# ADC.net
KiCad netlist of a schematic drawn in Altium Designer
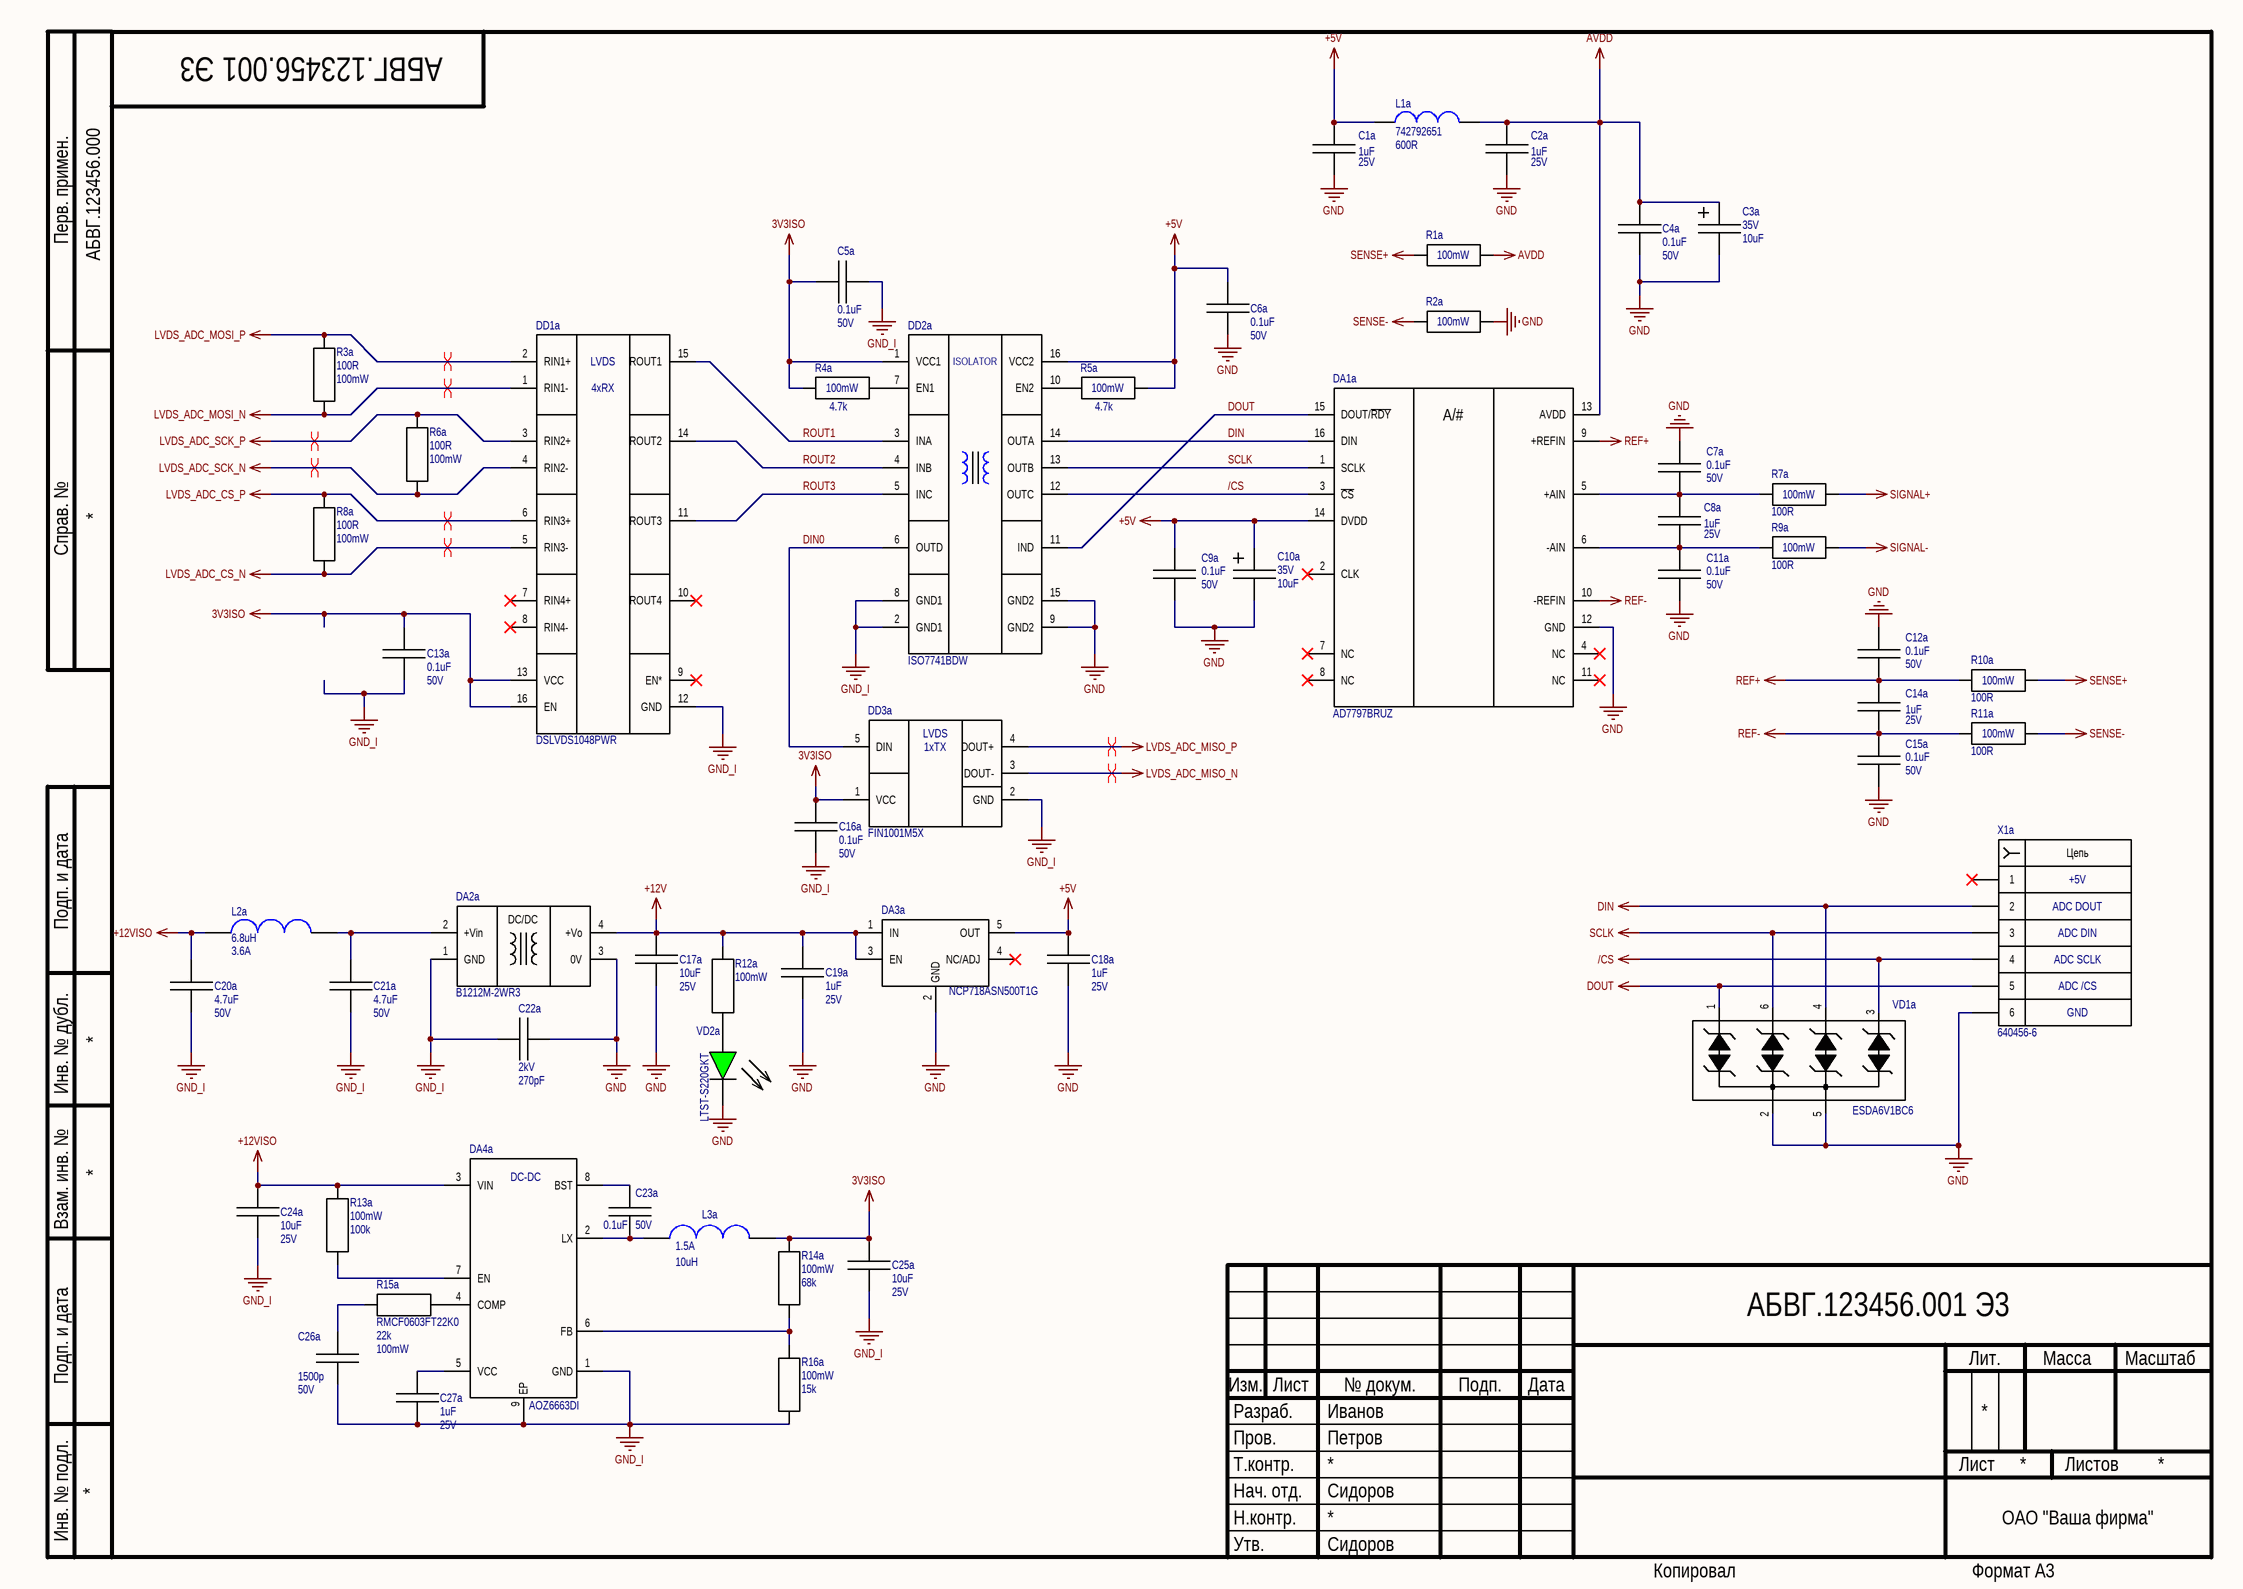
[diagram p0: ADC.SchDoc]

(export (version "E")
  (design (tool "Eeschema 10.0.6"))
  (components
    (comp (ref "C1a")
      (value "TMK107BJ105KA-T")
      (footprint "CAP 0603 IPC MAX")
      (description "CAP SMD CER 1UF 25V X5R 0603")
      (fields
        (field (name "TOLERANCE") "10%")
        (field (name "CAPACITANCE") "1uF")
        (field (name "RATED VOLTAGE") "25V")
      )
      (libsource (lib "Passive components") (part "TMK107BJ105KA-T"))
    )
    (comp (ref "C2a")
      (value "TMK107BJ105KA-T")
      (footprint "CAP 0603 IPC MAX")
      (description "CAP SMD CER 1UF 25V X5R 0603")
      (fields
        (field (name "TOLERANCE") "10%")
        (field (name "CAPACITANCE") "1uF")
        (field (name "RATED VOLTAGE") "25V")
      )
      (libsource (lib "Passive components") (part "TMK107BJ105KA-T"))
    )
    (comp (ref "C3a")
      (value "TAJD106M035RNJ")
      (footprint "CAP 2917 (D)")
      (description "CAP TANT 10UF 20% 35V 2917")
      (fields
        (field (name "TOLERANCE") "20%")
        (field (name "RATED VOLTAGE") "35V")
        (field (name "CAPACITANCE") "10uF")
      )
      (libsource (lib "Passive components") (part "TAJD106M035RNJ"))
    )
    (comp (ref "C4a")
      (value "GCM188R71H104KA57D")
      (footprint "CAP 0603 IPC MAX")
      (description "CAP SMD CER 0.1UF 50V X7R 0603")
      (fields
        (field (name "TOLERANCE") "10%")
        (field (name "CAPACITANCE") "0.1uF")
        (field (name "RATED VOLTAGE") "50V")
      )
      (libsource (lib "Passive components") (part "GCM188R71H104KA57D"))
    )
    (comp (ref "C5a")
      (value "GCM188R71H104KA57D")
      (footprint "CAP 0603 IPC MAX")
      (description "CAP SMD CER 0.1UF 50V X7R 0603")
      (fields
        (field (name "TOLERANCE") "10%")
        (field (name "CAPACITANCE") "0.1uF")
        (field (name "RATED VOLTAGE") "50V")
      )
      (libsource (lib "Passive components") (part "GCM188R71H104KA57D"))
    )
    (comp (ref "C6a")
      (value "GCM188R71H104KA57D")
      (footprint "CAP 0603 IPC MAX")
      (description "CAP SMD CER 0.1UF 50V X7R 0603")
      (fields
        (field (name "TOLERANCE") "10%")
        (field (name "CAPACITANCE") "0.1uF")
        (field (name "RATED VOLTAGE") "50V")
      )
      (libsource (lib "Passive components") (part "GCM188R71H104KA57D"))
    )
    (comp (ref "C7a")
      (value "GCM188R71H104KA57D")
      (footprint "CAP 0603 IPC MAX")
      (description "CAP SMD CER 0.1UF 50V X7R 0603")
      (fields
        (field (name "TOLERANCE") "10%")
        (field (name "CAPACITANCE") "0.1uF")
        (field (name "RATED VOLTAGE") "50V")
      )
      (libsource (lib "Passive components") (part "GCM188R71H104KA57D"))
    )
    (comp (ref "C8a")
      (value "TMK107BJ105KA-T")
      (footprint "CAP 0603 IPC MAX")
      (description "CAP SMD CER 1UF 25V X5R 0603")
      (fields
        (field (name "TOLERANCE") "10%")
        (field (name "CAPACITANCE") "1uF")
        (field (name "RATED VOLTAGE") "25V")
      )
      (libsource (lib "Passive components") (part "TMK107BJ105KA-T"))
    )
    (comp (ref "C9a")
      (value "GCM188R71H104KA57D")
      (footprint "CAP 0603 IPC MAX")
      (description "CAP SMD CER 0.1UF 50V X7R 0603")
      (fields
        (field (name "TOLERANCE") "10%")
        (field (name "CAPACITANCE") "0.1uF")
        (field (name "RATED VOLTAGE") "50V")
      )
      (libsource (lib "Passive components") (part "GCM188R71H104KA57D"))
    )
    (comp (ref "C10a")
      (value "TAJD106M035RNJ")
      (footprint "CAP 2917 (D)")
      (description "CAP TANT 10UF 20% 35V 2917")
      (fields
        (field (name "TOLERANCE") "20%")
        (field (name "RATED VOLTAGE") "35V")
        (field (name "CAPACITANCE") "10uF")
      )
      (libsource (lib "Passive components") (part "TAJD106M035RNJ"))
    )
    (comp (ref "C11a")
      (value "GCM188R71H104KA57D")
      (footprint "CAP 0603 IPC MAX")
      (description "CAP SMD CER 0.1UF 50V X7R 0603")
      (fields
        (field (name "TOLERANCE") "10%")
        (field (name "CAPACITANCE") "0.1uF")
        (field (name "RATED VOLTAGE") "50V")
      )
      (libsource (lib "Passive components") (part "GCM188R71H104KA57D"))
    )
    (comp (ref "C12a")
      (value "GCM188R71H104KA57D")
      (footprint "CAP 0603 IPC MAX")
      (description "CAP SMD CER 0.1UF 50V X7R 0603")
      (fields
        (field (name "TOLERANCE") "10%")
        (field (name "CAPACITANCE") "0.1uF")
        (field (name "RATED VOLTAGE") "50V")
      )
      (libsource (lib "Passive components") (part "GCM188R71H104KA57D"))
    )
    (comp (ref "C13a")
      (value "GCM188R71H104KA57D")
      (footprint "CAP 0603 IPC MAX")
      (description "CAP SMD CER 0.1UF 50V X7R 0603")
      (fields
        (field (name "TOLERANCE") "10%")
        (field (name "CAPACITANCE") "0.1uF")
        (field (name "RATED VOLTAGE") "50V")
      )
      (libsource (lib "Passive components") (part "GCM188R71H104KA57D"))
    )
    (comp (ref "C14a")
      (value "TMK107BJ105KA-T")
      (footprint "CAP 0603 IPC MAX")
      (description "CAP SMD CER 1UF 25V X5R 0603")
      (fields
        (field (name "TOLERANCE") "10%")
        (field (name "CAPACITANCE") "1uF")
        (field (name "RATED VOLTAGE") "25V")
      )
      (libsource (lib "Passive components") (part "TMK107BJ105KA-T"))
    )
    (comp (ref "C15a")
      (value "GCM188R71H104KA57D")
      (footprint "CAP 0603 IPC MAX")
      (description "CAP SMD CER 0.1UF 50V X7R 0603")
      (fields
        (field (name "TOLERANCE") "10%")
        (field (name "CAPACITANCE") "0.1uF")
        (field (name "RATED VOLTAGE") "50V")
      )
      (libsource (lib "Passive components") (part "GCM188R71H104KA57D"))
    )
    (comp (ref "C16a")
      (value "GCM188R71H104KA57D")
      (footprint "CAP 0603 IPC MAX")
      (description "CAP SMD CER 0.1UF 50V X7R 0603")
      (fields
        (field (name "TOLERANCE") "10%")
        (field (name "CAPACITANCE") "0.1uF")
        (field (name "RATED VOLTAGE") "50V")
      )
      (libsource (lib "Passive components") (part "GCM188R71H104KA57D"))
    )
    (comp (ref "C17a")
      (value "CL31B106KAHNNNE")
      (footprint "CAP 1206 IPC MAX")
      (description "CAP SMD CER 10UF 25V X7R 1206")
      (fields
        (field (name "TOLERANCE") "10%")
        (field (name "CAPACITANCE") "10uF")
        (field (name "RATED VOLTAGE") "25V")
      )
      (libsource (lib "Passive components") (part "CL31B106KAHNNNE"))
    )
    (comp (ref "C18a")
      (value "TMK107BJ105KA-T")
      (footprint "CAP 0603 IPC MAX")
      (description "CAP SMD CER 1UF 25V X5R 0603")
      (fields
        (field (name "TOLERANCE") "10%")
        (field (name "CAPACITANCE") "1uF")
        (field (name "RATED VOLTAGE") "25V")
      )
      (libsource (lib "Passive components") (part "TMK107BJ105KA-T"))
    )
    (comp (ref "C19a")
      (value "TMK107BJ105KA-T")
      (footprint "CAP 0603 IPC MAX")
      (description "CAP SMD CER 1UF 25V X5R 0603")
      (fields
        (field (name "TOLERANCE") "10%")
        (field (name "CAPACITANCE") "1uF")
        (field (name "RATED VOLTAGE") "25V")
      )
      (libsource (lib "Passive components") (part "TMK107BJ105KA-T"))
    )
    (comp (ref "C20a")
      (value "CL21A475KBQNNNE")
      (footprint "CAP 0805 IPC MAX")
      (description "CAP SMD CER 4.7UF 50V X5R 0805")
      (fields
        (field (name "TOLERANCE") "10%")
        (field (name "CAPACITANCE") "4.7uF")
        (field (name "RATED VOLTAGE") "50V")
      )
      (libsource (lib "Passive components") (part "CL21A475KBQNNNE"))
    )
    (comp (ref "C21a")
      (value "CL21A475KBQNNNE")
      (footprint "CAP 0805 IPC MAX")
      (description "CAP SMD CER 4.7UF 50V X5R 0805")
      (fields
        (field (name "TOLERANCE") "10%")
        (field (name "CAPACITANCE") "4.7uF")
        (field (name "RATED VOLTAGE") "50V")
      )
      (libsource (lib "Passive components") (part "CL21A475KBQNNNE"))
    )
    (comp (ref "C22a")
      (value "PHE448SB3270JR06")
      (footprint "CAP RADIAL L18.0 W5.0 H10.5 P15.0")
      (description "CAP FILM 270PF 5% 2KVDC RADIAL")
      (fields
        (field (name "TOLERANCE") "5%")
        (field (name "RATED VOLTAGE") "2kV")
        (field (name "CAPACITANCE") "270pF")
      )
      (libsource (lib "Passive components") (part "PHE448SB3270JR06"))
    )
    (comp (ref "C23a")
      (value "GCM188R71H104KA57D")
      (footprint "CAP 0603 IPC MAX")
      (description "CAP SMD CER 0.1UF 50V X7R 0603")
      (fields
        (field (name "TOLERANCE") "10%")
        (field (name "CAPACITANCE") "0.1uF")
        (field (name "RATED VOLTAGE") "50V")
      )
      (libsource (lib "Passive components") (part "GCM188R71H104KA57D"))
    )
    (comp (ref "C24a")
      (value "CL31B106KAHNNNE")
      (footprint "CAP 1206 IPC MAX")
      (description "CAP SMD CER 10UF 25V X7R 1206")
      (fields
        (field (name "TOLERANCE") "10%")
        (field (name "CAPACITANCE") "10uF")
        (field (name "RATED VOLTAGE") "25V")
      )
      (libsource (lib "Passive components") (part "CL31B106KAHNNNE"))
    )
    (comp (ref "C25a")
      (value "CL31B106KAHNNNE")
      (footprint "CAP 1206 IPC MAX")
      (description "CAP SMD CER 10UF 25V X7R 1206")
      (fields
        (field (name "TOLERANCE") "10%")
        (field (name "CAPACITANCE") "10uF")
        (field (name "RATED VOLTAGE") "25V")
      )
      (libsource (lib "Passive components") (part "CL31B106KAHNNNE"))
    )
    (comp (ref "C26a")
      (value "GRM1885C1H152JA01D")
      (footprint "CAP 0603 IPC MAX")
      (description "CAP SMD CER 1500PF 50V C0G/NP0 0603")
      (fields
        (field (name "TOLERANCE") "5%")
        (field (name "CAPACITANCE") "1500p")
        (field (name "RATED VOLTAGE") "50V")
      )
      (libsource (lib "Passive components") (part "GRM1885C1H152JA01D"))
    )
    (comp (ref "C27a")
      (value "TMK107BJ105KA-T")
      (footprint "CAP 0603 IPC MAX")
      (description "CAP SMD CER 1UF 25V X5R 0603")
      (fields
        (field (name "TOLERANCE") "10%")
        (field (name "CAPACITANCE") "1uF")
        (field (name "RATED VOLTAGE") "25V")
      )
      (libsource (lib "Passive components") (part "TMK107BJ105KA-T"))
    )
    (comp (ref "DA1a")
      (value "AD7797BRUZ")
      (footprint "TSSOP-16")
      (description "IC ADC 24BIT SIGMA-DELTA 16TSSOP")
      (libsource (lib "Digital") (part "AD7797BRUZ"))
    )
    (comp (ref "DA2a")
      (value "B1212M-2WR3")
      (footprint "B1212M-2WR3")
      (description "DC DC CONVERTER 12V 2W")
      (libsource (lib "Power") (part "B1212M-2WR3"))
    )
    (comp (ref "DA3a")
      (value "NCP718ASN500T1G")
      (footprint "TSOT-23-5")
      (description "IC REG LINEAR 5V 300MA TSOT23-5")
      (libsource (lib "Power") (part "NCP718ASN500T1G"))
    )
    (comp (ref "DA4a")
      (value "AOZ6663DI")
      (footprint "DFN 3x3-8L")
      (description "IC REG BUCK ADJ 3A 8DFN")
      (libsource (lib "Power") (part "AOZ6663DI"))
    )
    (comp (ref "DD1a")
      (value "DSLVDS1048PWR")
      (footprint "TSSOP-16")
      (description "IC RECEIVER LVDS FULL 0/4 16TSSOP")
      (libsource (lib "Digital") (part "DSLVDS1048PWR"))
    )
    (comp (ref "DD2a")
      (value "ISO7741BDW")
      (footprint "SOIC-16 IPC MAX")
      (description "DIG ISO - MYNA - QUAD")
      (libsource (lib "Digital") (part "ISO7741BDW"))
    )
    (comp (ref "DD3a")
      (value "FIN1001M5X")
      (footprint "SOT-23-5")
      (description "IC DRIVER LVDS 1/0 SOT23-5")
      (libsource (lib "Digital") (part "FIN1001M5X"))
    )
    (comp (ref "L1a")
      (value "742792651")
      (footprint "IND 0603 IPC MAX")
      (description "FERRITE BEAD 600 OHM 0603 1LN")
      (fields (field (name "INMEDANCE @ 100MHZ") "600R"))
      (libsource (lib "Passive components") (part "742792651"))
    )
    (comp (ref "L2a")
      (value "VLS6045EX-6R8M")
      (footprint "VLS6045EX")
      (description "FIXED IND 6.8UH 3.6A 36 MOHM SMD")
      (fields (field (name "INDUCTANCE") "6.8uH") (field (name "CURRENT RATING") "3.6A"))
      (libsource (lib "Passive components") (part "VLS6045EX-6R8M"))
    )
    (comp (ref "L3a")
      (value "ASPI-4030S-100M-T")
      (footprint "ASPI-4030S")
      (description "FIXED IND 10UH 1.5A 100 MOHM SMD")
      (fields (field (name "INDUCTANCE") "10uH") (field (name "CURRENT RATING") "1.5A"))
      (libsource (lib "Passive components") (part "ASPI-4030S-100M-T"))
    )
    (comp (ref "R1a")
      (value "RMCF0603ZT0R00")
      (footprint "RES 0603 IPC MAX")
      (description "RES SMD 0 OHM 1% 1/10W 0603")
      (fields (field (name "TOLERANCE") "1%") (field (name "RATED POWER") "100mW"))
      (libsource (lib "Passive components") (part "RMCF0603ZT0R00"))
    )
    (comp (ref "R2a")
      (value "RMCF0603ZT0R00")
      (footprint "RES 0603 IPC MAX")
      (description "RES SMD 0 OHM 1% 1/10W 0603")
      (fields (field (name "TOLERANCE") "1%") (field (name "RATED POWER") "100mW"))
      (libsource (lib "Passive components") (part "RMCF0603ZT0R00"))
    )
    (comp (ref "R3a")
      (value "RMCF0603FT100R")
      (footprint "RES 0603 IPC MAX")
      (description "RES SMD 100 OHM 1% 1/10W 0603")
      (fields
        (field (name "TOLERANCE") "1%")
        (field (name "RESISTANCE") "100R")
        (field (name "RATED POWER") "100mW")
      )
      (libsource (lib "Passive components") (part "RMCF0603FT100R"))
    )
    (comp (ref "R4a")
      (value "RMCF0603FT4K70")
      (footprint "RES 0603 IPC MAX")
      (description "RES SMD 4.7k OHM 1% 1/10W 0603")
      (fields
        (field (name "TOLERANCE") "1%")
        (field (name "RATED POWER") "100mW")
        (field (name "RESISTANCE") "4.7k")
      )
      (libsource (lib "Passive components") (part "RMCF0603FT4K70"))
    )
    (comp (ref "R5a")
      (value "RMCF0603FT4K70")
      (footprint "RES 0603 IPC MAX")
      (description "RES SMD 4.7k OHM 1% 1/10W 0603")
      (fields
        (field (name "TOLERANCE") "1%")
        (field (name "RATED POWER") "100mW")
        (field (name "RESISTANCE") "4.7k")
      )
      (libsource (lib "Passive components") (part "RMCF0603FT4K70"))
    )
    (comp (ref "R6a")
      (value "RMCF0603FT100R")
      (footprint "RES 0603 IPC MAX")
      (description "RES SMD 100 OHM 1% 1/10W 0603")
      (fields
        (field (name "TOLERANCE") "1%")
        (field (name "RESISTANCE") "100R")
        (field (name "RATED POWER") "100mW")
      )
      (libsource (lib "Passive components") (part "RMCF0603FT100R"))
    )
    (comp (ref "R7a")
      (value "RMCF0603FT100R")
      (footprint "RES 0603 IPC MAX")
      (description "RES SMD 100 OHM 1% 1/10W 0603")
      (fields
        (field (name "TOLERANCE") "1%")
        (field (name "RESISTANCE") "100R")
        (field (name "RATED POWER") "100mW")
      )
      (libsource (lib "Passive components") (part "RMCF0603FT100R"))
    )
    (comp (ref "R8a")
      (value "RMCF0603FT100R")
      (footprint "RES 0603 IPC MAX")
      (description "RES SMD 100 OHM 1% 1/10W 0603")
      (fields
        (field (name "TOLERANCE") "1%")
        (field (name "RESISTANCE") "100R")
        (field (name "RATED POWER") "100mW")
      )
      (libsource (lib "Passive components") (part "RMCF0603FT100R"))
    )
    (comp (ref "R9a")
      (value "RMCF0603FT100R")
      (footprint "RES 0603 IPC MAX")
      (description "RES SMD 100 OHM 1% 1/10W 0603")
      (fields
        (field (name "TOLERANCE") "1%")
        (field (name "RESISTANCE") "100R")
        (field (name "RATED POWER") "100mW")
      )
      (libsource (lib "Passive components") (part "RMCF0603FT100R"))
    )
    (comp (ref "R10a")
      (value "RMCF0603FT100R")
      (footprint "RES 0603 IPC MAX")
      (description "RES SMD 100 OHM 1% 1/10W 0603")
      (fields
        (field (name "TOLERANCE") "1%")
        (field (name "RESISTANCE") "100R")
        (field (name "RATED POWER") "100mW")
      )
      (libsource (lib "Passive components") (part "RMCF0603FT100R"))
    )
    (comp (ref "R11a")
      (value "RMCF0603FT100R")
      (footprint "RES 0603 IPC MAX")
      (description "RES SMD 100 OHM 1% 1/10W 0603")
      (fields
        (field (name "TOLERANCE") "1%")
        (field (name "RESISTANCE") "100R")
        (field (name "RATED POWER") "100mW")
      )
      (libsource (lib "Passive components") (part "RMCF0603FT100R"))
    )
    (comp (ref "R12a")
      (value "RMCF0603FT2K00")
      (footprint "RES 0603 IPC MAX")
      (description "RES SMD 2K OHM 1% 1/10W 0603")
      (fields (field (name "TOLERANCE") "1%") (field (name "RATED POWER") "100mW"))
      (libsource (lib "Passive components") (part "RMCF0603FT2K00"))
    )
    (comp (ref "R13a")
      (value "RMCF0603FT100K")
      (footprint "RES 0603 IPC MAX")
      (description "RES SMD 100K OHM 5% 1/10W 0603")
      (fields
        (field (name "TOLERANCE") "5%")
        (field (name "POWER RATED") "100mW")
        (field (name "RESISTANCE") "100k")
      )
      (libsource (lib "Passive components") (part "RMCF0603FT100K"))
    )
    (comp (ref "R14a")
      (value "RMCF0603FT68K0")
      (footprint "RES 0603 IPC MAX")
      (description "RES SMD 68K OHM 1% 1/10W 0603")
      (fields
        (field (name "TOLERANCE") "1%")
        (field (name "POWER RATED") "100mW")
        (field (name "RESISTANCE") "68k")
      )
      (libsource (lib "Passive components") (part "RMCF0603FT68K0"))
    )
    (comp (ref "R15a")
      (value "RMCF0603FT22K0")
      (footprint "RES 0603 IPC MAX")
      (description "RES SMD 22K OHM 1% 1/10W 0603")
      (fields
        (field (name "TOLERANCE") "1%")
        (field (name "RESISTANCE") "22k")
        (field (name "POWER RATED") "100mW")
      )
      (libsource (lib "Passive components") (part "RMCF0603FT22K0"))
    )
    (comp (ref "R16a")
      (value "RMCF0603FT15K0")
      (footprint "RES 0603 IPC MAX")
      (description "RES SMD 15K OHM 1% 1/10W 0603")
      (fields
        (field (name "TOLERANCE") "1%")
        (field (name "POWER RATED") "100mW")
        (field (name "RESISTANCE") "15k")
      )
      (libsource (lib "Passive components") (part "RMCF0603FT15K0"))
    )
    (comp (ref "VD1a")
      (value "ESDA6V1BC6")
      (footprint "SOT-23-6")
      (description "TVS DIODE 5VWM SOT23-6")
      (libsource (lib "Diodes") (part "ESDA6V1BC6"))
    )
    (comp (ref "VD2a")
      (value "LTST-S220GKT")
      (footprint "0805 DIODE")
      (description "LED GREEN CLEAR SMD R/A")
      (libsource (lib "Diodes") (part "LTST-S220GKT"))
    )
    (comp (ref "X1a")
      (value "640456-6")
      (footprint "640456-6")
      (description "CONN HEADER VERT 6POS 2.54MM")
      (libsource (lib "Connectors") (part "640456-6"))
    )
  )
  (nets
    (net (code "1") (name "+5V") (class "Default")
      (node (ref "C10a") (pin "1") (pinfunction "1_1") (pintype "passive"))
      (node (ref "C18a") (pin "1") (pinfunction "1_1") (pintype "passive"))
      (node (ref "C1a") (pin "1") (pinfunction "1_1") (pintype "passive"))
      (node (ref "C6a") (pin "1") (pinfunction "1_1") (pintype "passive"))
      (node (ref "C9a") (pin "1") (pinfunction "1_1") (pintype "passive"))
      (node (ref "DA1a") (pin "14") (pinfunction "DVDD_14") (pintype "passive"))
      (node (ref "DA3a") (pin "5") (pinfunction "OUT_5") (pintype "passive"))
      (node (ref "DD2a") (pin "16") (pinfunction "VCC2_16") (pintype "passive"))
      (node (ref "L1a") (pin "1") (pinfunction "1_1") (pintype "passive"))
      (node (ref "R5a") (pin "1") (pinfunction "1_1") (pintype "passive"))
    )
    (net (code "2") (name "+12V") (class "Default")
      (node (ref "C17a") (pin "1") (pinfunction "1_1") (pintype "passive"))
      (node (ref "C19a") (pin "1") (pinfunction "1_1") (pintype "passive"))
      (node (ref "DA2a") (pin "4") (pinfunction "+Vo_4") (pintype "passive"))
      (node (ref "DA3a") (pin "1") (pinfunction "IN_1") (pintype "passive"))
      (node (ref "DA3a") (pin "3") (pinfunction "EN_3") (pintype "passive"))
      (node (ref "R12a") (pin "2") (pinfunction "2_2") (pintype "passive"))
    )
    (net (code "3") (name "+12VISO") (class "Default")
      (node (ref "C20a") (pin "1") (pinfunction "1_1") (pintype "passive"))
      (node (ref "C24a") (pin "1") (pinfunction "1_1") (pintype "passive"))
      (node (ref "DA4a") (pin "3") (pinfunction "VIN_3") (pintype "passive"))
      (node (ref "L2a") (pin "1") (pinfunction "1_1") (pintype "passive"))
      (node (ref "R13a") (pin "1") (pinfunction "1_1") (pintype "passive"))
    )
    (net (code "4") (name "/DIN0") (class "Default")
      (node (ref "DD2a") (pin "6") (pinfunction "OUTD_6") (pintype "passive"))
      (node (ref "DD3a") (pin "5") (pinfunction "DIN_5") (pintype "passive"))
    )
    (net (code "5") (name "/ROUT1") (class "Default")
      (node (ref "DD1a") (pin "15") (pinfunction "ROUT1_15") (pintype "passive"))
      (node (ref "DD2a") (pin "3") (pinfunction "INA_3") (pintype "passive"))
    )
    (net (code "6") (name "/ROUT2") (class "Default")
      (node (ref "DD1a") (pin "14") (pinfunction "ROUT2_14") (pintype "passive"))
      (node (ref "DD2a") (pin "4") (pinfunction "INB_4") (pintype "passive"))
    )
    (net (code "7") (name "/ROUT3") (class "Default")
      (node (ref "DD1a") (pin "11") (pinfunction "ROUT3_11") (pintype "passive"))
      (node (ref "DD2a") (pin "5") (pinfunction "INC_5") (pintype "passive"))
    )
    (net (code "8") (name "3V3ISO") (class "Default")
      (node (ref "C13a") (pin "1") (pinfunction "1_1") (pintype "passive"))
      (node (ref "C16a") (pin "1") (pinfunction "1_1") (pintype "passive"))
      (node (ref "C25a") (pin "1") (pinfunction "1_1") (pintype "passive"))
      (node (ref "C5a") (pin "2") (pinfunction "2_2") (pintype "passive"))
      (node (ref "DD1a") (pin "13") (pinfunction "VCC_13") (pintype "passive"))
      (node (ref "DD1a") (pin "16") (pinfunction "EN_16") (pintype "passive"))
      (node (ref "DD2a") (pin "1") (pinfunction "VCC1_1") (pintype "passive"))
      (node (ref "DD3a") (pin "1") (pinfunction "VCC_1") (pintype "passive"))
      (node (ref "L3a") (pin "2") (pinfunction "2_2") (pintype "passive"))
      (node (ref "R14a") (pin "1") (pinfunction "1_1") (pintype "passive"))
      (node (ref "R4a") (pin "2") (pinfunction "2_2") (pintype "passive"))
    )
    (net (code "9") (name "AVDD") (class "Default")
      (node (ref "C2a") (pin "1") (pinfunction "1_1") (pintype "passive"))
      (node (ref "C3a") (pin "1") (pinfunction "1_1") (pintype "passive"))
      (node (ref "C4a") (pin "1") (pinfunction "1_1") (pintype "passive"))
      (node (ref "DA1a") (pin "13") (pinfunction "AVDD_13") (pintype "passive"))
      (node (ref "L1a") (pin "2") (pinfunction "2_2") (pintype "passive"))
      (node (ref "R1a") (pin "2") (pinfunction "2_2") (pintype "passive"))
    )
    (net (code "10") (name "DIN") (class "Default")
      (node (ref "DA1a") (pin "16") (pinfunction "DIN_16") (pintype "passive"))
      (node (ref "DD2a") (pin "14") (pinfunction "OUTA_14") (pintype "passive"))
      (node (ref "VD1a") (pin "4") (pinfunction "4_4") (pintype "passive"))
      (node (ref "X1a") (pin "2") (pinfunction "2_2") (pintype "passive"))
    )
    (net (code "11") (name "DOUT") (class "Default")
      (node (ref "DA1a") (pin "15") (pinfunction "DOUT/~{RDY}_15") (pintype "passive"))
      (node (ref "DD2a") (pin "11") (pinfunction "IND_11") (pintype "passive"))
      (node (ref "VD1a") (pin "1") (pinfunction "1_1") (pintype "passive"))
      (node (ref "X1a") (pin "5") (pinfunction "5_5") (pintype "passive"))
    )
    (net (code "12") (name "GND") (class "Default")
      (node (ref "C10a") (pin "2") (pinfunction "2_2") (pintype "passive"))
      (node (ref "C11a") (pin "2") (pinfunction "2_2") (pintype "passive"))
      (node (ref "C12a") (pin "1") (pinfunction "1_1") (pintype "passive"))
      (node (ref "C15a") (pin "2") (pinfunction "2_2") (pintype "passive"))
      (node (ref "C17a") (pin "2") (pinfunction "2_2") (pintype "passive"))
      (node (ref "C18a") (pin "2") (pinfunction "2_2") (pintype "passive"))
      (node (ref "C19a") (pin "2") (pinfunction "2_2") (pintype "passive"))
      (node (ref "C1a") (pin "2") (pinfunction "2_2") (pintype "passive"))
      (node (ref "C22a") (pin "1") (pinfunction "1_1") (pintype "passive"))
      (node (ref "C2a") (pin "2") (pinfunction "2_2") (pintype "passive"))
      (node (ref "C3a") (pin "2") (pinfunction "2_2") (pintype "passive"))
      (node (ref "C4a") (pin "2") (pinfunction "2_2") (pintype "passive"))
      (node (ref "C6a") (pin "2") (pinfunction "2_2") (pintype "passive"))
      (node (ref "C7a") (pin "1") (pinfunction "1_1") (pintype "passive"))
      (node (ref "C9a") (pin "2") (pinfunction "2_2") (pintype "passive"))
      (node (ref "DA1a") (pin "12") (pinfunction "GND_12") (pintype "passive"))
      (node (ref "DA2a") (pin "3") (pinfunction "0V_3") (pintype "passive"))
      (node (ref "DA3a") (pin "2") (pinfunction "GND_2") (pintype "passive"))
      (node (ref "DD2a") (pin "15") (pinfunction "GND2_15") (pintype "passive"))
      (node (ref "DD2a") (pin "9") (pinfunction "GND2_9") (pintype "passive"))
      (node (ref "R2a") (pin "2") (pinfunction "2_2") (pintype "passive"))
      (node (ref "VD1a") (pin "2") (pinfunction "2_2") (pintype "passive"))
      (node (ref "VD1a") (pin "5") (pinfunction "5_5") (pintype "passive"))
      (node (ref "VD2a") (pin "2") (pinfunction "2_2") (pintype "passive"))
      (node (ref "X1a") (pin "6") (pinfunction "6_6") (pintype "passive"))
    )
    (net (code "13") (name "GND_I") (class "Default")
      (node (ref "C13a") (pin "2") (pinfunction "2_2") (pintype "passive"))
      (node (ref "C16a") (pin "2") (pinfunction "2_2") (pintype "passive"))
      (node (ref "C20a") (pin "2") (pinfunction "2_2") (pintype "passive"))
      (node (ref "C21a") (pin "2") (pinfunction "2_2") (pintype "passive"))
      (node (ref "C22a") (pin "2") (pinfunction "2_2") (pintype "passive"))
      (node (ref "C24a") (pin "2") (pinfunction "2_2") (pintype "passive"))
      (node (ref "C25a") (pin "2") (pinfunction "2_2") (pintype "passive"))
      (node (ref "C26a") (pin "2") (pinfunction "2_2") (pintype "passive"))
      (node (ref "C27a") (pin "2") (pinfunction "2_2") (pintype "passive"))
      (node (ref "C5a") (pin "1") (pinfunction "1_1") (pintype "passive"))
      (node (ref "DA2a") (pin "1") (pinfunction "GND_1") (pintype "passive"))
      (node (ref "DA4a") (pin "1") (pinfunction "GND_1") (pintype "passive"))
      (node (ref "DA4a") (pin "9") (pinfunction "EP_9") (pintype "passive"))
      (node (ref "DD1a") (pin "12") (pinfunction "GND_12") (pintype "passive"))
      (node (ref "DD2a") (pin "2") (pinfunction "GND1_2") (pintype "passive"))
      (node (ref "DD2a") (pin "8") (pinfunction "GND1_8") (pintype "passive"))
      (node (ref "DD3a") (pin "2") (pinfunction "GND_2") (pintype "passive"))
      (node (ref "R16a") (pin "1") (pinfunction "1_1") (pintype "passive"))
    )
    (net (code "14") (name "LVDS_ADC_CS_N") (class "Default")
      (node (ref "DD1a") (pin "5") (pinfunction "RIN3-_5") (pintype "passive"))
      (node (ref "R8a") (pin "1") (pinfunction "1_1") (pintype "passive"))
    )
    (net (code "15") (name "LVDS_ADC_CS_P") (class "Default")
      (node (ref "DD1a") (pin "6") (pinfunction "RIN3+_6") (pintype "passive"))
      (node (ref "R8a") (pin "2") (pinfunction "2_2") (pintype "passive"))
    )
    (net (code "16") (name "LVDS_ADC_MISO_N") (class "Default")
      (node (ref "DD3a") (pin "3") (pinfunction "DOUT-_3") (pintype "passive"))
    )
    (net (code "17") (name "LVDS_ADC_MISO_P") (class "Default")
      (node (ref "DD3a") (pin "4") (pinfunction "DOUT+_4") (pintype "passive"))
    )
    (net (code "18") (name "LVDS_ADC_MOSI_N") (class "Default")
      (node (ref "DD1a") (pin "1") (pinfunction "RIN1-_1") (pintype "passive"))
      (node (ref "R3a") (pin "1") (pinfunction "1_1") (pintype "passive"))
    )
    (net (code "19") (name "LVDS_ADC_MOSI_P") (class "Default")
      (node (ref "DD1a") (pin "2") (pinfunction "RIN1+_2") (pintype "passive"))
      (node (ref "R3a") (pin "2") (pinfunction "2_2") (pintype "passive"))
    )
    (net (code "20") (name "LVDS_ADC_SCK_N") (class "Default")
      (node (ref "DD1a") (pin "4") (pinfunction "RIN2-_4") (pintype "passive"))
      (node (ref "R6a") (pin "1") (pinfunction "1_1") (pintype "passive"))
    )
    (net (code "21") (name "LVDS_ADC_SCK_P") (class "Default")
      (node (ref "DD1a") (pin "3") (pinfunction "RIN2+_3") (pintype "passive"))
      (node (ref "R6a") (pin "2") (pinfunction "2_2") (pintype "passive"))
    )
    (net (code "22") (name "Net-(C26a-Pad1)") (class "Default")
      (node (ref "C26a") (pin "1") (pinfunction "1_1") (pintype "passive"))
      (node (ref "R15a") (pin "1") (pinfunction "1_1") (pintype "passive"))
    )
    (net (code "23") (name "Net-(DA1a-+AIN)") (class "Default")
      (node (ref "C7a") (pin "2") (pinfunction "2_2") (pintype "passive"))
      (node (ref "C8a") (pin "1") (pinfunction "1_1") (pintype "passive"))
      (node (ref "DA1a") (pin "5") (pinfunction "+AIN_5") (pintype "passive"))
      (node (ref "R7a") (pin "2") (pinfunction "2_2") (pintype "passive"))
    )
    (net (code "24") (name "Net-(DA1a--AIN)") (class "Default")
      (node (ref "C11a") (pin "1") (pinfunction "1_1") (pintype "passive"))
      (node (ref "C8a") (pin "2") (pinfunction "2_2") (pintype "passive"))
      (node (ref "DA1a") (pin "6") (pinfunction "-AIN_6") (pintype "passive"))
      (node (ref "R9a") (pin "2") (pinfunction "2_2") (pintype "passive"))
    )
    (net (code "25") (name "Net-(DA2a-+Vin)") (class "Default")
      (node (ref "C21a") (pin "1") (pinfunction "1_1") (pintype "passive"))
      (node (ref "DA2a") (pin "2") (pinfunction "+Vin_2") (pintype "passive"))
      (node (ref "L2a") (pin "2") (pinfunction "2_2") (pintype "passive"))
    )
    (net (code "26") (name "Net-(DA4a-BST)") (class "Default")
      (node (ref "C23a") (pin "1") (pinfunction "1_1") (pintype "passive"))
      (node (ref "DA4a") (pin "8") (pinfunction "BST_8") (pintype "passive"))
    )
    (net (code "27") (name "Net-(DA4a-COMP)") (class "Default")
      (node (ref "DA4a") (pin "4") (pinfunction "COMP_4") (pintype "passive"))
      (node (ref "R15a") (pin "2") (pinfunction "2_2") (pintype "passive"))
    )
    (net (code "28") (name "Net-(DA4a-EN)") (class "Default")
      (node (ref "DA4a") (pin "7") (pinfunction "EN_7") (pintype "passive"))
      (node (ref "R13a") (pin "2") (pinfunction "2_2") (pintype "passive"))
    )
    (net (code "29") (name "Net-(DA4a-FB)") (class "Default")
      (node (ref "DA4a") (pin "6") (pinfunction "FB_6") (pintype "passive"))
      (node (ref "R14a") (pin "2") (pinfunction "2_2") (pintype "passive"))
      (node (ref "R16a") (pin "2") (pinfunction "2_2") (pintype "passive"))
    )
    (net (code "30") (name "Net-(DA4a-LX)") (class "Default")
      (node (ref "C23a") (pin "2") (pinfunction "2_2") (pintype "passive"))
      (node (ref "DA4a") (pin "2") (pinfunction "LX_2") (pintype "passive"))
      (node (ref "L3a") (pin "1") (pinfunction "1_1") (pintype "passive"))
    )
    (net (code "31") (name "Net-(DA4a-VCC)") (class "Default")
      (node (ref "C27a") (pin "1") (pinfunction "1_1") (pintype "passive"))
      (node (ref "DA4a") (pin "5") (pinfunction "VCC_5") (pintype "passive"))
    )
    (net (code "32") (name "Net-(DD2a-EN1)") (class "Default")
      (node (ref "DD2a") (pin "7") (pinfunction "EN1_7") (pintype "passive"))
      (node (ref "R4a") (pin "1") (pinfunction "1_1") (pintype "passive"))
    )
    (net (code "33") (name "Net-(DD2a-EN2)") (class "Default")
      (node (ref "DD2a") (pin "10") (pinfunction "EN2_10") (pintype "passive"))
      (node (ref "R5a") (pin "2") (pinfunction "2_2") (pintype "passive"))
    )
    (net (code "34") (name "Net-(R12a-Pad1)") (class "Default")
      (node (ref "R12a") (pin "1") (pinfunction "1_1") (pintype "passive"))
      (node (ref "VD2a") (pin "1") (pinfunction "1_1") (pintype "passive"))
    )
    (net (code "35") (name "REF+") (class "Default")
      (node (ref "C12a") (pin "2") (pinfunction "2_2") (pintype "passive"))
      (node (ref "C14a") (pin "1") (pinfunction "1_1") (pintype "passive"))
      (node (ref "DA1a") (pin "9") (pinfunction "+REFIN_9") (pintype "passive"))
      (node (ref "R10a") (pin "2") (pinfunction "2_2") (pintype "passive"))
    )
    (net (code "36") (name "REF-") (class "Default")
      (node (ref "C14a") (pin "2") (pinfunction "2_2") (pintype "passive"))
      (node (ref "C15a") (pin "1") (pinfunction "1_1") (pintype "passive"))
      (node (ref "DA1a") (pin "10") (pinfunction "-REFIN_10") (pintype "passive"))
      (node (ref "R11a") (pin "2") (pinfunction "2_2") (pintype "passive"))
    )
    (net (code "37") (name "SCLK") (class "Default")
      (node (ref "DA1a") (pin "1") (pinfunction "SCLK_1") (pintype "passive"))
      (node (ref "DD2a") (pin "13") (pinfunction "OUTB_13") (pintype "passive"))
      (node (ref "VD1a") (pin "6") (pinfunction "6_6") (pintype "passive"))
      (node (ref "X1a") (pin "3") (pinfunction "3_3") (pintype "passive"))
    )
    (net (code "38") (name "SENSE+") (class "Default")
      (node (ref "R10a") (pin "1") (pinfunction "1_1") (pintype "passive"))
      (node (ref "R1a") (pin "1") (pinfunction "1_1") (pintype "passive"))
    )
    (net (code "39") (name "SENSE-") (class "Default")
      (node (ref "R11a") (pin "1") (pinfunction "1_1") (pintype "passive"))
      (node (ref "R2a") (pin "1") (pinfunction "1_1") (pintype "passive"))
    )
    (net (code "40") (name "SIGNAL+") (class "Default")
      (node (ref "R7a") (pin "1") (pinfunction "1_1") (pintype "passive"))
    )
    (net (code "41") (name "SIGNAL-") (class "Default")
      (node (ref "R9a") (pin "1") (pinfunction "1_1") (pintype "passive"))
    )
    (net (code "42") (name "unconnected-(DA1a-CLK-Pad2)") (class "Default")
      (node (ref "DA1a") (pin "2") (pinfunction "CLK_2") (pintype "passive+no_connect"))
    )
    (net (code "43") (name "unconnected-(DA1a-NC-Pad4)") (class "Default")
      (node (ref "DA1a") (pin "4") (pinfunction "NC_4") (pintype "passive+no_connect"))
    )
    (net (code "44") (name "unconnected-(DA1a-NC-Pad7)") (class "Default")
      (node (ref "DA1a") (pin "7") (pinfunction "NC_7") (pintype "passive+no_connect"))
    )
    (net (code "45") (name "unconnected-(DA1a-NC-Pad8)") (class "Default")
      (node (ref "DA1a") (pin "8") (pinfunction "NC_8") (pintype "passive+no_connect"))
    )
    (net (code "46") (name "unconnected-(DA1a-NC-Pad11)") (class "Default")
      (node (ref "DA1a") (pin "11") (pinfunction "NC_11") (pintype "passive+no_connect"))
    )
    (net (code "47") (name "unconnected-(DA3a-NC{slash}ADJ-Pad4)") (class "Default")
      (node (ref "DA3a") (pin "4") (pinfunction "NC/ADJ_4") (pintype "passive+no_connect"))
    )
    (net (code "48") (name "unconnected-(DD1a-EN*-Pad9)") (class "Default")
      (node (ref "DD1a") (pin "9") (pinfunction "EN*_9") (pintype "passive+no_connect"))
    )
    (net (code "49") (name "unconnected-(DD1a-RIN4+-Pad7)") (class "Default")
      (node (ref "DD1a") (pin "7") (pinfunction "RIN4+_7") (pintype "passive+no_connect"))
    )
    (net (code "50") (name "unconnected-(DD1a-RIN4--Pad8)") (class "Default")
      (node (ref "DD1a") (pin "8") (pinfunction "RIN4-_8") (pintype "passive+no_connect"))
    )
    (net (code "51") (name "unconnected-(DD1a-ROUT4-Pad10)") (class "Default")
      (node (ref "DD1a") (pin "10") (pinfunction "ROUT4_10") (pintype "passive+no_connect"))
    )
    (net (code "52") (name "unconnected-(X1a-Pad1)") (class "Default")
      (node (ref "X1a") (pin "1") (pinfunction "1_1") (pintype "passive+no_connect"))
    )
    (net (code "53") (name "{slash}CS") (class "Default")
      (node (ref "DA1a") (pin "3") (pinfunction "~{CS}_3") (pintype "passive"))
      (node (ref "DD2a") (pin "12") (pinfunction "OUTC_12") (pintype "passive"))
      (node (ref "VD1a") (pin "3") (pinfunction "3_3") (pintype "passive"))
      (node (ref "X1a") (pin "4") (pinfunction "4_4") (pintype "passive"))
    )
  )
)
